# SoC_FPGA_128-131_GTY.net
KiCad netlist of a schematic drawn in Altium Designer
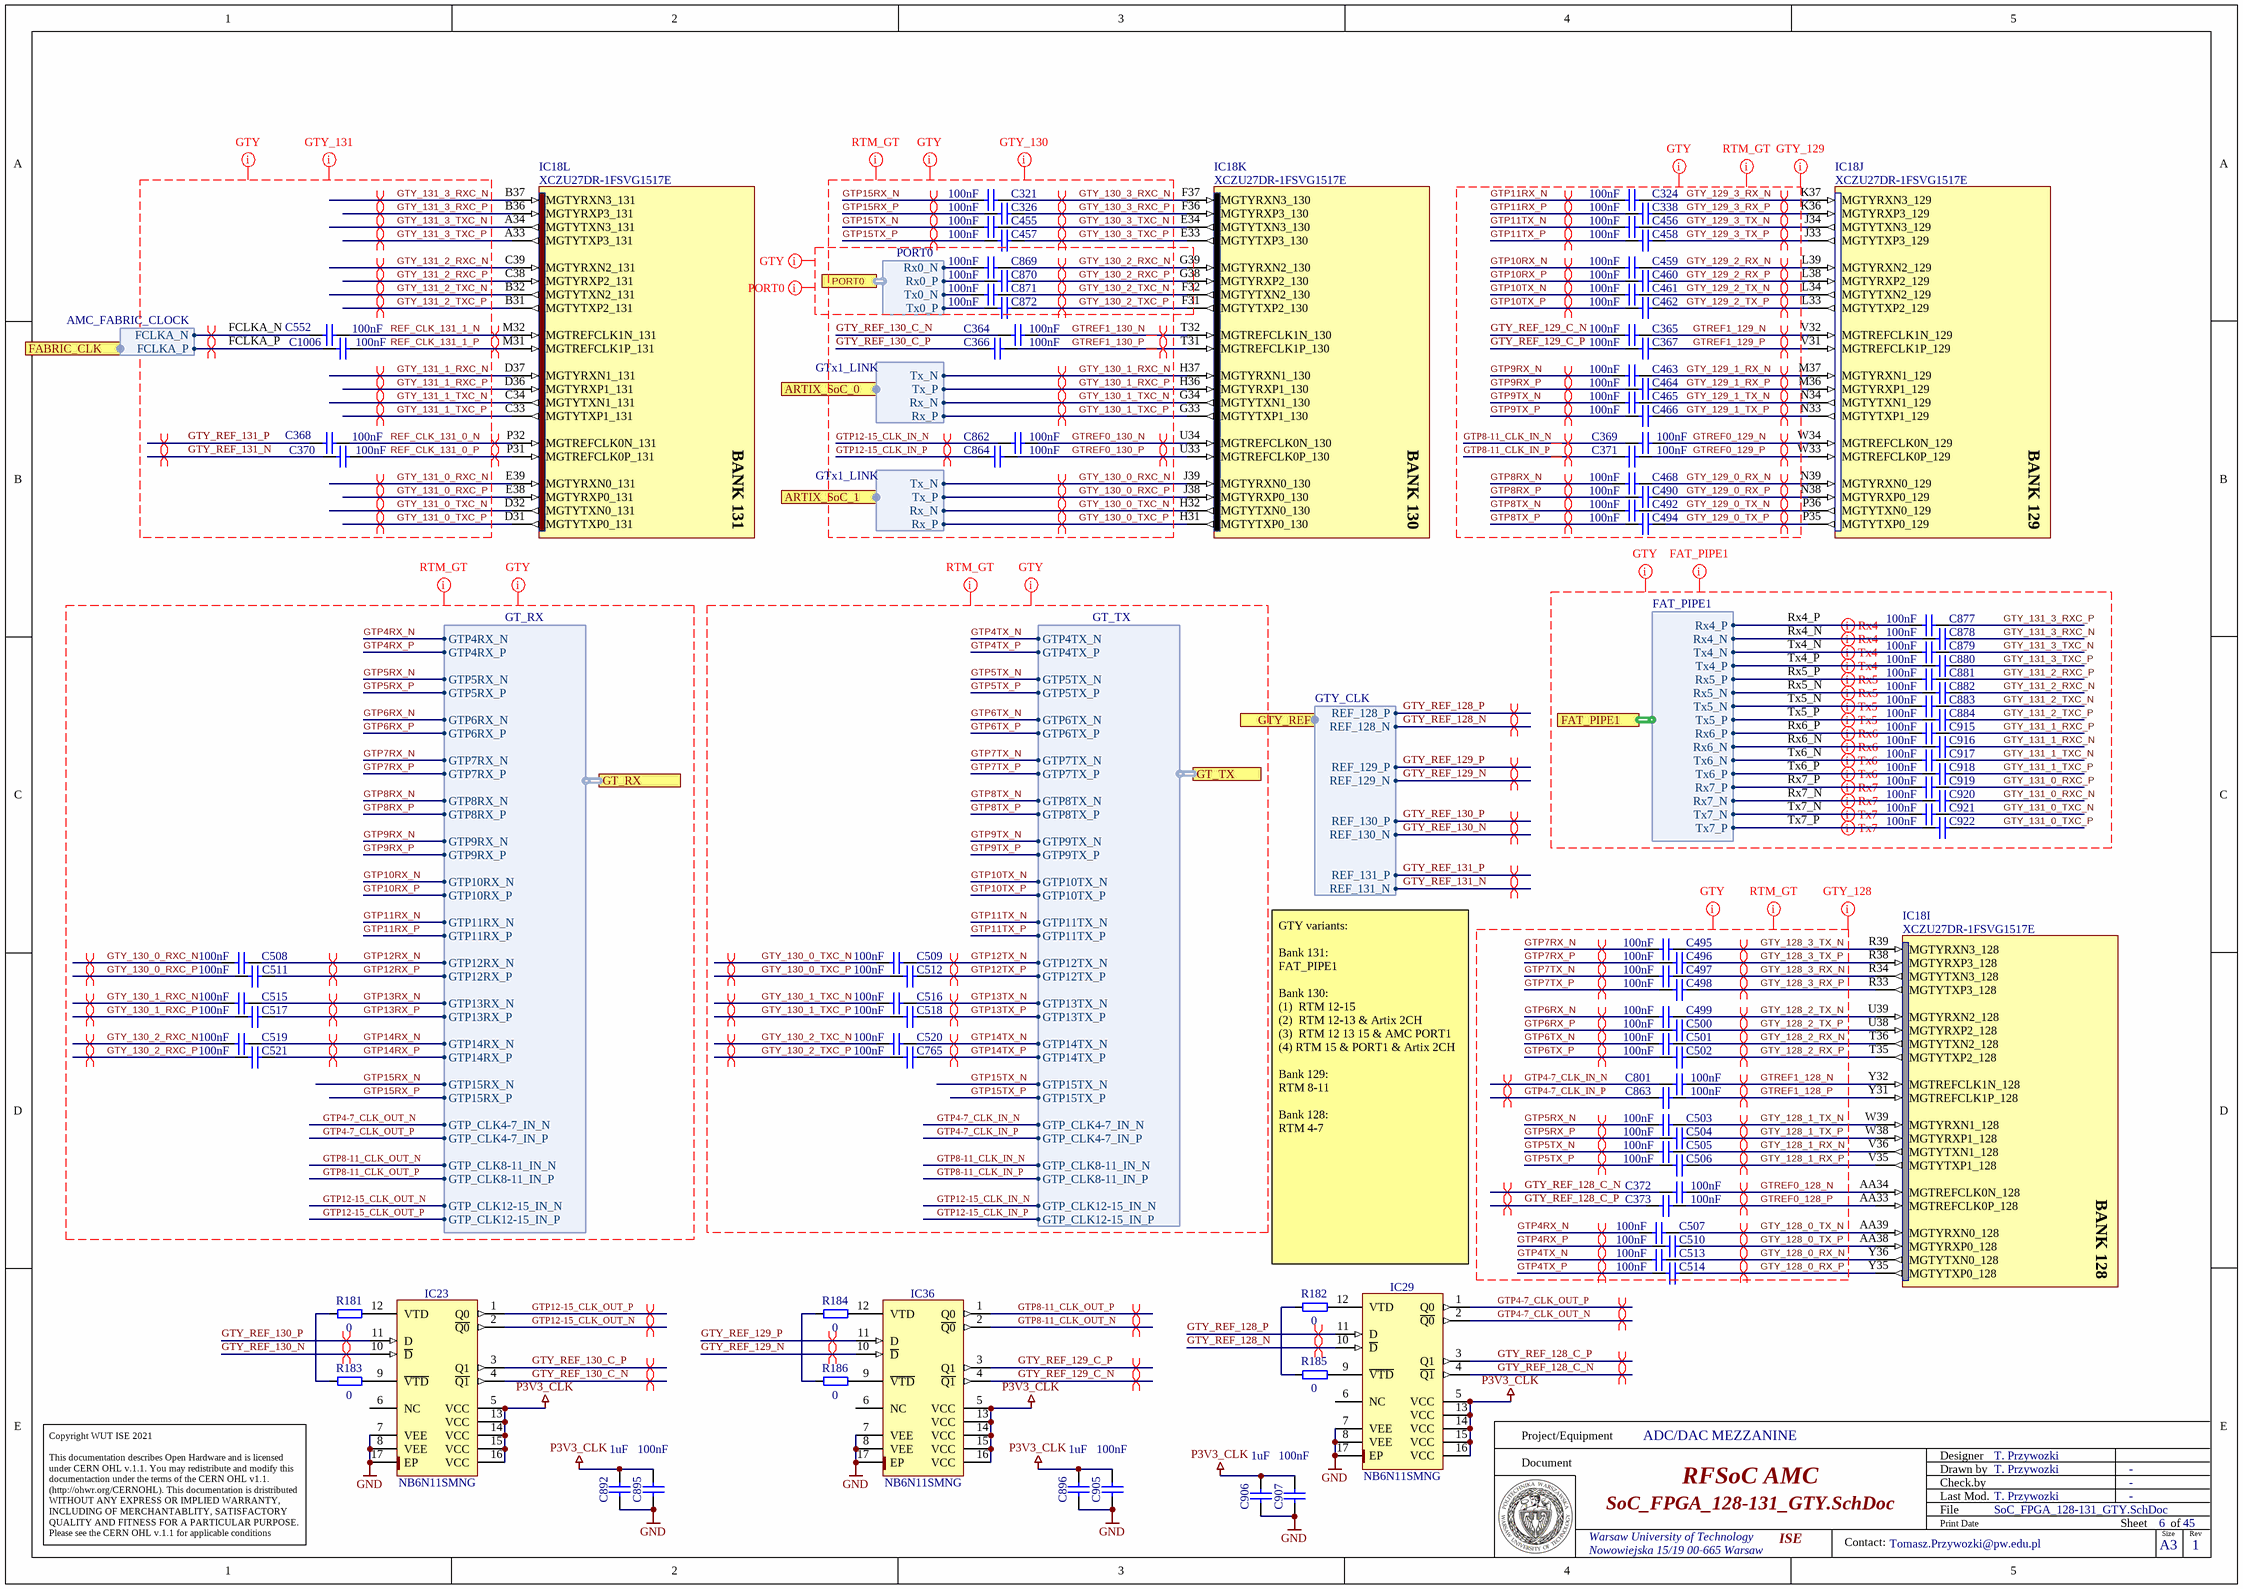
[diagram p0: SoC_FPGA_128-131_GTY.SchDoc]

(export (version "E")
  (design (tool "Eeschema 10.0.6"))
  (components
    (comp (ref "C321")
      (value "100nF")
      (footprint "CAPC0603X33N")
      (description "Non-polarised capacitor")
      (fields
        (field (name "MANUFACTURER PART NUMBER") "CC0201_100NF_6.3V_10%_X5R")
        (field (name "MANUFACTURER") "GENERIC")
        (field (name "AUTHOR") "CERN DEM JLC")
      )
      (libsource (lib "Capacitors") (part "Capacitor - non polarized"))
    )
    (comp (ref "C324")
      (value "100nF")
      (footprint "CAPC0603X33N")
      (description "Non-polarised capacitor")
      (fields
        (field (name "MANUFACTURER PART NUMBER") "CC0201_100NF_6.3V_10%_X5R")
        (field (name "MANUFACTURER") "GENERIC")
        (field (name "AUTHOR") "CERN DEM JLC")
      )
      (libsource (lib "Capacitors") (part "Capacitor - non polarized"))
    )
    (comp (ref "C326")
      (value "100nF")
      (footprint "CAPC0603X33N")
      (description "Non-polarised capacitor")
      (fields
        (field (name "MANUFACTURER PART NUMBER") "CC0201_100NF_6.3V_10%_X5R")
        (field (name "MANUFACTURER") "GENERIC")
        (field (name "AUTHOR") "CERN DEM JLC")
      )
      (libsource (lib "Capacitors") (part "Capacitor - non polarized"))
    )
    (comp (ref "C338")
      (value "100nF")
      (footprint "CAPC0603X33N")
      (description "Non-polarised capacitor")
      (fields
        (field (name "MANUFACTURER PART NUMBER") "CC0201_100NF_6.3V_10%_X5R")
        (field (name "MANUFACTURER") "GENERIC")
        (field (name "AUTHOR") "CERN DEM JLC")
      )
      (libsource (lib "Capacitors") (part "Capacitor - non polarized"))
    )
    (comp (ref "C364")
      (value "100nF")
      (footprint "CAPC0603X33N")
      (description "Non-polarised capacitor")
      (fields
        (field (name "PART NUMBER") "CC0201_100NF_6.3V_10%_X5R")
        (field (name "VOLTAGE") "6.3V")
        (field (name "AUTHOR") "CERN DEM JLC")
      )
      (libsource (lib "Capacitors") (part "Capacitor - non polarized"))
    )
    (comp (ref "C365")
      (value "100nF")
      (footprint "CAPC0603X33N")
      (description "Non-polarised capacitor")
      (fields
        (field (name "MANUFACTURER PART NUMBER") "CC0201_100NF_6.3V_10%_X5R")
        (field (name "MANUFACTURER") "GENERIC")
        (field (name "AUTHOR") "CERN DEM JLC")
      )
      (libsource (lib "Capacitors") (part "Capacitor - non polarized"))
    )
    (comp (ref "C366")
      (value "100nF")
      (footprint "CAPC0603X33N")
      (description "Non-polarised capacitor")
      (fields
        (field (name "PART NUMBER") "CC0201_100NF_6.3V_10%_X5R")
        (field (name "VOLTAGE") "6.3V")
        (field (name "AUTHOR") "CERN DEM JLC")
      )
      (libsource (lib "Capacitors") (part "Capacitor - non polarized"))
    )
    (comp (ref "C367")
      (value "100nF")
      (footprint "CAPC0603X33N")
      (description "Non-polarised capacitor")
      (fields
        (field (name "MANUFACTURER PART NUMBER") "CC0201_100NF_6.3V_10%_X5R")
        (field (name "MANUFACTURER") "GENERIC")
        (field (name "AUTHOR") "CERN DEM JLC")
      )
      (libsource (lib "Capacitors") (part "Capacitor - non polarized"))
    )
    (comp (ref "C368")
      (value "100nF")
      (footprint "CAPC0603X33N")
      (description "Non-polarised capacitor")
      (fields
        (field (name "MANUFACTURER PART NUMBER") "CC0201_100NF_6.3V_10%_X5R")
        (field (name "MANUFACTURER") "GENERIC")
        (field (name "AUTHOR") "CERN DEM JLC")
      )
      (libsource (lib "Capacitors") (part "Capacitor - non polarized"))
    )
    (comp (ref "C369")
      (value "100nF")
      (footprint "CAPC0603X33N")
      (description "Non-polarised capacitor")
      (fields
        (field (name "PART NUMBER") "CC0201_100NF_6.3V_10%_X5R")
        (field (name "VOLTAGE") "6.3V")
        (field (name "AUTHOR") "CERN DEM JLC")
      )
      (libsource (lib "Capacitors") (part "Capacitor - non polarized"))
    )
    (comp (ref "C370")
      (value "100nF")
      (footprint "CAPC0603X33N")
      (description "Non-polarised capacitor")
      (fields
        (field (name "MANUFACTURER PART NUMBER") "CC0201_100NF_6.3V_10%_X5R")
        (field (name "MANUFACTURER") "GENERIC")
        (field (name "AUTHOR") "CERN DEM JLC")
      )
      (libsource (lib "Capacitors") (part "Capacitor - non polarized"))
    )
    (comp (ref "C371")
      (value "100nF")
      (footprint "CAPC0603X33N")
      (description "Non-polarised capacitor")
      (fields
        (field (name "PART NUMBER") "CC0201_100NF_6.3V_10%_X5R")
        (field (name "VOLTAGE") "6.3V")
        (field (name "AUTHOR") "CERN DEM JLC")
      )
      (libsource (lib "Capacitors") (part "Capacitor - non polarized"))
    )
    (comp (ref "C372")
      (value "100nF")
      (footprint "CAPC0603X33N")
      (description "Non-polarised capacitor")
      (fields
        (field (name "PART NUMBER") "CC0201_100NF_6.3V_10%_X5R")
        (field (name "VOLTAGE") "6.3V")
        (field (name "AUTHOR") "CERN DEM JLC")
      )
      (libsource (lib "Capacitors") (part "Capacitor - non polarized"))
    )
    (comp (ref "C373")
      (value "100nF")
      (footprint "CAPC0603X33N")
      (description "Non-polarised capacitor")
      (fields
        (field (name "PART NUMBER") "CC0201_100NF_6.3V_10%_X5R")
        (field (name "VOLTAGE") "6.3V")
        (field (name "AUTHOR") "CERN DEM JLC")
      )
      (libsource (lib "Capacitors") (part "Capacitor - non polarized"))
    )
    (comp (ref "C455")
      (value "100nF")
      (footprint "CAPC0603X33N")
      (description "Non-polarised capacitor")
      (fields
        (field (name "MANUFACTURER PART NUMBER") "CC0201_100NF_6.3V_10%_X5R")
        (field (name "MANUFACTURER") "GENERIC")
        (field (name "AUTHOR") "CERN DEM JLC")
      )
      (libsource (lib "Capacitors") (part "Capacitor - non polarized"))
    )
    (comp (ref "C456")
      (value "100nF")
      (footprint "CAPC0603X33N")
      (description "Non-polarised capacitor")
      (fields
        (field (name "MANUFACTURER PART NUMBER") "CC0201_100NF_6.3V_10%_X5R")
        (field (name "MANUFACTURER") "GENERIC")
        (field (name "AUTHOR") "CERN DEM JLC")
      )
      (libsource (lib "Capacitors") (part "Capacitor - non polarized"))
    )
    (comp (ref "C457")
      (value "100nF")
      (footprint "CAPC0603X33N")
      (description "Non-polarised capacitor")
      (fields
        (field (name "MANUFACTURER PART NUMBER") "CC0201_100NF_6.3V_10%_X5R")
        (field (name "MANUFACTURER") "GENERIC")
        (field (name "AUTHOR") "CERN DEM JLC")
      )
      (libsource (lib "Capacitors") (part "Capacitor - non polarized"))
    )
    (comp (ref "C458")
      (value "100nF")
      (footprint "CAPC0603X33N")
      (description "Non-polarised capacitor")
      (fields
        (field (name "MANUFACTURER PART NUMBER") "CC0201_100NF_6.3V_10%_X5R")
        (field (name "MANUFACTURER") "GENERIC")
        (field (name "AUTHOR") "CERN DEM JLC")
      )
      (libsource (lib "Capacitors") (part "Capacitor - non polarized"))
    )
    (comp (ref "C459")
      (value "100nF")
      (footprint "CAPC0603X33N")
      (description "Non-polarised capacitor")
      (fields
        (field (name "MANUFACTURER PART NUMBER") "CC0201_100NF_6.3V_10%_X5R")
        (field (name "MANUFACTURER") "GENERIC")
        (field (name "AUTHOR") "CERN DEM JLC")
      )
      (libsource (lib "Capacitors") (part "Capacitor - non polarized"))
    )
    (comp (ref "C460")
      (value "100nF")
      (footprint "CAPC0603X33N")
      (description "Non-polarised capacitor")
      (fields
        (field (name "MANUFACTURER PART NUMBER") "CC0201_100NF_6.3V_10%_X5R")
        (field (name "MANUFACTURER") "GENERIC")
        (field (name "AUTHOR") "CERN DEM JLC")
      )
      (libsource (lib "Capacitors") (part "Capacitor - non polarized"))
    )
    (comp (ref "C461")
      (value "100nF")
      (footprint "CAPC0603X33N")
      (description "Non-polarised capacitor")
      (fields
        (field (name "MANUFACTURER PART NUMBER") "CC0201_100NF_6.3V_10%_X5R")
        (field (name "MANUFACTURER") "GENERIC")
        (field (name "AUTHOR") "CERN DEM JLC")
      )
      (libsource (lib "Capacitors") (part "Capacitor - non polarized"))
    )
    (comp (ref "C462")
      (value "100nF")
      (footprint "CAPC0603X33N")
      (description "Non-polarised capacitor")
      (fields
        (field (name "MANUFACTURER PART NUMBER") "CC0201_100NF_6.3V_10%_X5R")
        (field (name "MANUFACTURER") "GENERIC")
        (field (name "AUTHOR") "CERN DEM JLC")
      )
      (libsource (lib "Capacitors") (part "Capacitor - non polarized"))
    )
    (comp (ref "C463")
      (value "100nF")
      (footprint "CAPC0603X33N")
      (description "Non-polarised capacitor")
      (fields
        (field (name "MANUFACTURER PART NUMBER") "CC0201_100NF_6.3V_10%_X5R")
        (field (name "MANUFACTURER") "GENERIC")
        (field (name "AUTHOR") "CERN DEM JLC")
      )
      (libsource (lib "Capacitors") (part "Capacitor - non polarized"))
    )
    (comp (ref "C464")
      (value "100nF")
      (footprint "CAPC0603X33N")
      (description "Non-polarised capacitor")
      (fields
        (field (name "MANUFACTURER PART NUMBER") "CC0201_100NF_6.3V_10%_X5R")
        (field (name "MANUFACTURER") "GENERIC")
        (field (name "AUTHOR") "CERN DEM JLC")
      )
      (libsource (lib "Capacitors") (part "Capacitor - non polarized"))
    )
    (comp (ref "C465")
      (value "100nF")
      (footprint "CAPC0603X33N")
      (description "Non-polarised capacitor")
      (fields
        (field (name "MANUFACTURER PART NUMBER") "CC0201_100NF_6.3V_10%_X5R")
        (field (name "MANUFACTURER") "GENERIC")
        (field (name "AUTHOR") "CERN DEM JLC")
      )
      (libsource (lib "Capacitors") (part "Capacitor - non polarized"))
    )
    (comp (ref "C466")
      (value "100nF")
      (footprint "CAPC0603X33N")
      (description "Non-polarised capacitor")
      (fields
        (field (name "MANUFACTURER PART NUMBER") "CC0201_100NF_6.3V_10%_X5R")
        (field (name "MANUFACTURER") "GENERIC")
        (field (name "AUTHOR") "CERN DEM JLC")
      )
      (libsource (lib "Capacitors") (part "Capacitor - non polarized"))
    )
    (comp (ref "C468")
      (value "100nF")
      (footprint "CAPC0603X33N")
      (description "Non-polarised capacitor")
      (fields
        (field (name "MANUFACTURER PART NUMBER") "CC0201_100NF_6.3V_10%_X5R")
        (field (name "MANUFACTURER") "GENERIC")
        (field (name "AUTHOR") "CERN DEM JLC")
      )
      (libsource (lib "Capacitors") (part "Capacitor - non polarized"))
    )
    (comp (ref "C490")
      (value "100nF")
      (footprint "CAPC0603X33N")
      (description "Non-polarised capacitor")
      (fields
        (field (name "MANUFACTURER PART NUMBER") "CC0201_100NF_6.3V_10%_X5R")
        (field (name "MANUFACTURER") "GENERIC")
        (field (name "AUTHOR") "CERN DEM JLC")
      )
      (libsource (lib "Capacitors") (part "Capacitor - non polarized"))
    )
    (comp (ref "C492")
      (value "100nF")
      (footprint "CAPC0603X33N")
      (description "Non-polarised capacitor")
      (fields
        (field (name "MANUFACTURER PART NUMBER") "CC0201_100NF_6.3V_10%_X5R")
        (field (name "MANUFACTURER") "GENERIC")
        (field (name "AUTHOR") "CERN DEM JLC")
      )
      (libsource (lib "Capacitors") (part "Capacitor - non polarized"))
    )
    (comp (ref "C494")
      (value "100nF")
      (footprint "CAPC0603X33N")
      (description "Non-polarised capacitor")
      (fields
        (field (name "MANUFACTURER PART NUMBER") "CC0201_100NF_6.3V_10%_X5R")
        (field (name "MANUFACTURER") "GENERIC")
        (field (name "AUTHOR") "CERN DEM JLC")
      )
      (libsource (lib "Capacitors") (part "Capacitor - non polarized"))
    )
    (comp (ref "C495")
      (value "100nF")
      (footprint "CAPC0603X33N")
      (description "Non-polarised capacitor")
      (fields
        (field (name "MANUFACTURER PART NUMBER") "CC0201_100NF_6.3V_10%_X5R")
        (field (name "MANUFACTURER") "GENERIC")
        (field (name "AUTHOR") "CERN DEM JLC")
      )
      (libsource (lib "Capacitors") (part "Capacitor - non polarized"))
    )
    (comp (ref "C496")
      (value "100nF")
      (footprint "CAPC0603X33N")
      (description "Non-polarised capacitor")
      (fields
        (field (name "MANUFACTURER PART NUMBER") "CC0201_100NF_6.3V_10%_X5R")
        (field (name "MANUFACTURER") "GENERIC")
        (field (name "AUTHOR") "CERN DEM JLC")
      )
      (libsource (lib "Capacitors") (part "Capacitor - non polarized"))
    )
    (comp (ref "C497")
      (value "100nF")
      (footprint "CAPC0603X33N")
      (description "Non-polarised capacitor")
      (fields
        (field (name "MANUFACTURER PART NUMBER") "CC0201_100NF_6.3V_10%_X5R")
        (field (name "MANUFACTURER") "GENERIC")
        (field (name "AUTHOR") "CERN DEM JLC")
      )
      (libsource (lib "Capacitors") (part "Capacitor - non polarized"))
    )
    (comp (ref "C498")
      (value "100nF")
      (footprint "CAPC0603X33N")
      (description "Non-polarised capacitor")
      (fields
        (field (name "MANUFACTURER PART NUMBER") "CC0201_100NF_6.3V_10%_X5R")
        (field (name "MANUFACTURER") "GENERIC")
        (field (name "AUTHOR") "CERN DEM JLC")
      )
      (libsource (lib "Capacitors") (part "Capacitor - non polarized"))
    )
    (comp (ref "C499")
      (value "100nF")
      (footprint "CAPC0603X33N")
      (description "Non-polarised capacitor")
      (fields
        (field (name "MANUFACTURER PART NUMBER") "CC0201_100NF_6.3V_10%_X5R")
        (field (name "MANUFACTURER") "GENERIC")
        (field (name "AUTHOR") "CERN DEM JLC")
      )
      (libsource (lib "Capacitors") (part "Capacitor - non polarized"))
    )
    (comp (ref "C500")
      (value "100nF")
      (footprint "CAPC0603X33N")
      (description "Non-polarised capacitor")
      (fields
        (field (name "MANUFACTURER PART NUMBER") "CC0201_100NF_6.3V_10%_X5R")
        (field (name "MANUFACTURER") "GENERIC")
        (field (name "AUTHOR") "CERN DEM JLC")
      )
      (libsource (lib "Capacitors") (part "Capacitor - non polarized"))
    )
    (comp (ref "C501")
      (value "100nF")
      (footprint "CAPC0603X33N")
      (description "Non-polarised capacitor")
      (fields
        (field (name "MANUFACTURER PART NUMBER") "CC0201_100NF_6.3V_10%_X5R")
        (field (name "MANUFACTURER") "GENERIC")
        (field (name "AUTHOR") "CERN DEM JLC")
      )
      (libsource (lib "Capacitors") (part "Capacitor - non polarized"))
    )
    (comp (ref "C502")
      (value "100nF")
      (footprint "CAPC0603X33N")
      (description "Non-polarised capacitor")
      (fields
        (field (name "MANUFACTURER PART NUMBER") "CC0201_100NF_6.3V_10%_X5R")
        (field (name "MANUFACTURER") "GENERIC")
        (field (name "AUTHOR") "CERN DEM JLC")
      )
      (libsource (lib "Capacitors") (part "Capacitor - non polarized"))
    )
    (comp (ref "C503")
      (value "100nF")
      (footprint "CAPC0603X33N")
      (description "Non-polarised capacitor")
      (fields
        (field (name "MANUFACTURER PART NUMBER") "CC0201_100NF_6.3V_10%_X5R")
        (field (name "MANUFACTURER") "GENERIC")
        (field (name "AUTHOR") "CERN DEM JLC")
      )
      (libsource (lib "Capacitors") (part "Capacitor - non polarized"))
    )
    (comp (ref "C504")
      (value "100nF")
      (footprint "CAPC0603X33N")
      (description "Non-polarised capacitor")
      (fields
        (field (name "MANUFACTURER PART NUMBER") "CC0201_100NF_6.3V_10%_X5R")
        (field (name "MANUFACTURER") "GENERIC")
        (field (name "AUTHOR") "CERN DEM JLC")
      )
      (libsource (lib "Capacitors") (part "Capacitor - non polarized"))
    )
    (comp (ref "C505")
      (value "100nF")
      (footprint "CAPC0603X33N")
      (description "Non-polarised capacitor")
      (fields
        (field (name "MANUFACTURER PART NUMBER") "CC0201_100NF_6.3V_10%_X5R")
        (field (name "MANUFACTURER") "GENERIC")
        (field (name "AUTHOR") "CERN DEM JLC")
      )
      (libsource (lib "Capacitors") (part "Capacitor - non polarized"))
    )
    (comp (ref "C506")
      (value "100nF")
      (footprint "CAPC0603X33N")
      (description "Non-polarised capacitor")
      (fields
        (field (name "MANUFACTURER PART NUMBER") "CC0201_100NF_6.3V_10%_X5R")
        (field (name "MANUFACTURER") "GENERIC")
        (field (name "AUTHOR") "CERN DEM JLC")
      )
      (libsource (lib "Capacitors") (part "Capacitor - non polarized"))
    )
    (comp (ref "C507")
      (value "100nF")
      (footprint "CAPC0603X33N")
      (description "Non-polarised capacitor")
      (fields
        (field (name "MANUFACTURER PART NUMBER") "CC0201_100NF_6.3V_10%_X5R")
        (field (name "MANUFACTURER") "GENERIC")
        (field (name "AUTHOR") "CERN DEM JLC")
      )
      (libsource (lib "Capacitors") (part "Capacitor - non polarized"))
    )
    (comp (ref "C508")
      (value "100nF")
      (footprint "CAPC0603X33N")
      (description "Non-polarised capacitor")
      (fields
        (field (name "MANUFACTURER PART NUMBER") "CC0201_100NF_6.3V_10%_X5R")
        (field (name "MANUFACTURER") "GENERIC")
        (field (name "AUTHOR") "CERN DEM JLC")
      )
      (libsource (lib "Capacitors") (part "Capacitor - non polarized"))
    )
    (comp (ref "C509")
      (value "100nF")
      (footprint "CAPC0603X33N")
      (description "Non-polarised capacitor")
      (fields
        (field (name "MANUFACTURER PART NUMBER") "CC0201_100NF_6.3V_10%_X5R")
        (field (name "MANUFACTURER") "GENERIC")
        (field (name "AUTHOR") "CERN DEM JLC")
      )
      (libsource (lib "Capacitors") (part "Capacitor - non polarized"))
    )
    (comp (ref "C510")
      (value "100nF")
      (footprint "CAPC0603X33N")
      (description "Non-polarised capacitor")
      (fields
        (field (name "MANUFACTURER PART NUMBER") "CC0201_100NF_6.3V_10%_X5R")
        (field (name "MANUFACTURER") "GENERIC")
        (field (name "AUTHOR") "CERN DEM JLC")
      )
      (libsource (lib "Capacitors") (part "Capacitor - non polarized"))
    )
    (comp (ref "C511")
      (value "100nF")
      (footprint "CAPC0603X33N")
      (description "Non-polarised capacitor")
      (fields
        (field (name "MANUFACTURER PART NUMBER") "CC0201_100NF_6.3V_10%_X5R")
        (field (name "MANUFACTURER") "GENERIC")
        (field (name "AUTHOR") "CERN DEM JLC")
      )
      (libsource (lib "Capacitors") (part "Capacitor - non polarized"))
    )
    (comp (ref "C512")
      (value "100nF")
      (footprint "CAPC0603X33N")
      (description "Non-polarised capacitor")
      (fields
        (field (name "MANUFACTURER PART NUMBER") "CC0201_100NF_6.3V_10%_X5R")
        (field (name "MANUFACTURER") "GENERIC")
        (field (name "AUTHOR") "CERN DEM JLC")
      )
      (libsource (lib "Capacitors") (part "Capacitor - non polarized"))
    )
    (comp (ref "C513")
      (value "100nF")
      (footprint "CAPC0603X33N")
      (description "Non-polarised capacitor")
      (fields
        (field (name "MANUFACTURER PART NUMBER") "CC0201_100NF_6.3V_10%_X5R")
        (field (name "MANUFACTURER") "GENERIC")
        (field (name "AUTHOR") "CERN DEM JLC")
      )
      (libsource (lib "Capacitors") (part "Capacitor - non polarized"))
    )
    (comp (ref "C514")
      (value "100nF")
      (footprint "CAPC0603X33N")
      (description "Non-polarised capacitor")
      (fields
        (field (name "MANUFACTURER PART NUMBER") "CC0201_100NF_6.3V_10%_X5R")
        (field (name "MANUFACTURER") "GENERIC")
        (field (name "AUTHOR") "CERN DEM JLC")
      )
      (libsource (lib "Capacitors") (part "Capacitor - non polarized"))
    )
    (comp (ref "C515")
      (value "100nF")
      (footprint "CAPC0603X33N")
      (description "Non-polarised capacitor")
      (fields
        (field (name "MANUFACTURER PART NUMBER") "CC0201_100NF_6.3V_10%_X5R")
        (field (name "MANUFACTURER") "GENERIC")
        (field (name "AUTHOR") "CERN DEM JLC")
      )
      (libsource (lib "Capacitors") (part "Capacitor - non polarized"))
    )
    (comp (ref "C516")
      (value "100nF")
      (footprint "CAPC0603X33N")
      (description "Non-polarised capacitor")
      (fields
        (field (name "MANUFACTURER PART NUMBER") "CC0201_100NF_6.3V_10%_X5R")
        (field (name "MANUFACTURER") "GENERIC")
        (field (name "AUTHOR") "CERN DEM JLC")
      )
      (libsource (lib "Capacitors") (part "Capacitor - non polarized"))
    )
    (comp (ref "C517")
      (value "100nF")
      (footprint "CAPC0603X33N")
      (description "Non-polarised capacitor")
      (fields
        (field (name "MANUFACTURER PART NUMBER") "CC0201_100NF_6.3V_10%_X5R")
        (field (name "MANUFACTURER") "GENERIC")
        (field (name "AUTHOR") "CERN DEM JLC")
      )
      (libsource (lib "Capacitors") (part "Capacitor - non polarized"))
    )
    (comp (ref "C518")
      (value "100nF")
      (footprint "CAPC0603X33N")
      (description "Non-polarised capacitor")
      (fields
        (field (name "MANUFACTURER PART NUMBER") "CC0201_100NF_6.3V_10%_X5R")
        (field (name "MANUFACTURER") "GENERIC")
        (field (name "AUTHOR") "CERN DEM JLC")
      )
      (libsource (lib "Capacitors") (part "Capacitor - non polarized"))
    )
    (comp (ref "C519")
      (value "100nF")
      (footprint "CAPC0603X33N")
      (description "Non-polarised capacitor")
      (fields
        (field (name "MANUFACTURER PART NUMBER") "CC0201_100NF_6.3V_10%_X5R")
        (field (name "MANUFACTURER") "GENERIC")
        (field (name "AUTHOR") "CERN DEM JLC")
      )
      (libsource (lib "Capacitors") (part "Capacitor - non polarized"))
    )
    (comp (ref "C520")
      (value "100nF")
      (footprint "CAPC0603X33N")
      (description "Non-polarised capacitor")
      (fields
        (field (name "MANUFACTURER PART NUMBER") "CC0201_100NF_6.3V_10%_X5R")
        (field (name "MANUFACTURER") "GENERIC")
        (field (name "AUTHOR") "CERN DEM JLC")
      )
      (libsource (lib "Capacitors") (part "Capacitor - non polarized"))
    )
    (comp (ref "C521")
      (value "100nF")
      (footprint "CAPC0603X33N")
      (description "Non-polarised capacitor")
      (fields
        (field (name "MANUFACTURER PART NUMBER") "CC0201_100NF_6.3V_10%_X5R")
        (field (name "MANUFACTURER") "GENERIC")
        (field (name "AUTHOR") "CERN DEM JLC")
      )
      (libsource (lib "Capacitors") (part "Capacitor - non polarized"))
    )
    (comp (ref "C552")
      (value "100nF")
      (footprint "CAPC0603X33N")
      (description "Non-polarised capacitor")
      (fields
        (field (name "MANUFACTURER PART NUMBER") "CC0201_100NF_6.3V_10%_X5R")
        (field (name "MANUFACTURER") "GENERIC")
        (field (name "AUTHOR") "CERN DEM JLC")
      )
      (libsource (lib "Capacitors") (part "Capacitor - non polarized"))
    )
    (comp (ref "C765")
      (value "100nF")
      (footprint "CAPC0603X33N")
      (description "Non-polarised capacitor")
      (fields
        (field (name "MANUFACTURER PART NUMBER") "CC0201_100NF_6.3V_10%_X5R")
        (field (name "MANUFACTURER") "GENERIC")
        (field (name "AUTHOR") "CERN DEM JLC")
      )
      (libsource (lib "Capacitors") (part "Capacitor - non polarized"))
    )
    (comp (ref "C801")
      (value "100nF")
      (footprint "CAPC0603X33N")
      (description "Non-polarised capacitor")
      (fields
        (field (name "PART NUMBER") "CC0201_100NF_6.3V_10%_X5R")
        (field (name "VOLTAGE") "6.3V")
        (field (name "AUTHOR") "CERN DEM JLC")
      )
      (libsource (lib "Capacitors") (part "Capacitor - non polarized"))
    )
    (comp (ref "C862")
      (value "100nF")
      (footprint "CAPC0603X33N")
      (description "Non-polarised capacitor")
      (fields
        (field (name "PART NUMBER") "CC0201_100NF_6.3V_10%_X5R")
        (field (name "VOLTAGE") "6.3V")
        (field (name "AUTHOR") "CERN DEM JLC")
      )
      (libsource (lib "Capacitors") (part "Capacitor - non polarized"))
    )
    (comp (ref "C863")
      (value "100nF")
      (footprint "CAPC0603X33N")
      (description "Non-polarised capacitor")
      (fields
        (field (name "PART NUMBER") "CC0201_100NF_6.3V_10%_X5R")
        (field (name "VOLTAGE") "6.3V")
        (field (name "AUTHOR") "CERN DEM JLC")
      )
      (libsource (lib "Capacitors") (part "Capacitor - non polarized"))
    )
    (comp (ref "C864")
      (value "100nF")
      (footprint "CAPC0603X33N")
      (description "Non-polarised capacitor")
      (fields
        (field (name "PART NUMBER") "CC0201_100NF_6.3V_10%_X5R")
        (field (name "VOLTAGE") "6.3V")
        (field (name "AUTHOR") "CERN DEM JLC")
      )
      (libsource (lib "Capacitors") (part "Capacitor - non polarized"))
    )
    (comp (ref "C869")
      (value "100nF")
      (footprint "CAPC0603X33N")
      (description "Non-polarised capacitor")
      (fields
        (field (name "MANUFACTURER PART NUMBER") "CC0201_100NF_6.3V_10%_X5R")
        (field (name "MANUFACTURER") "GENERIC")
        (field (name "AUTHOR") "CERN DEM JLC")
      )
      (libsource (lib "Capacitors") (part "Capacitor - non polarized"))
    )
    (comp (ref "C870")
      (value "100nF")
      (footprint "CAPC0603X33N")
      (description "Non-polarised capacitor")
      (fields
        (field (name "MANUFACTURER PART NUMBER") "CC0201_100NF_6.3V_10%_X5R")
        (field (name "MANUFACTURER") "GENERIC")
        (field (name "AUTHOR") "CERN DEM JLC")
      )
      (libsource (lib "Capacitors") (part "Capacitor - non polarized"))
    )
    (comp (ref "C871")
      (value "100nF")
      (footprint "CAPC0603X33N")
      (description "Non-polarised capacitor")
      (fields
        (field (name "MANUFACTURER PART NUMBER") "CC0201_100NF_6.3V_10%_X5R")
        (field (name "MANUFACTURER") "GENERIC")
        (field (name "AUTHOR") "CERN DEM JLC")
      )
      (libsource (lib "Capacitors") (part "Capacitor - non polarized"))
    )
    (comp (ref "C872")
      (value "100nF")
      (footprint "CAPC0603X33N")
      (description "Non-polarised capacitor")
      (fields
        (field (name "MANUFACTURER PART NUMBER") "CC0201_100NF_6.3V_10%_X5R")
        (field (name "MANUFACTURER") "GENERIC")
        (field (name "AUTHOR") "CERN DEM JLC")
      )
      (libsource (lib "Capacitors") (part "Capacitor - non polarized"))
    )
    (comp (ref "C877")
      (value "100nF")
      (footprint "CAPC0603X33N")
      (description "Non-polarised capacitor")
      (fields
        (field (name "MANUFACTURER PART NUMBER") "CC0201_100NF_6.3V_10%_X5R")
        (field (name "MANUFACTURER") "GENERIC")
        (field (name "AUTHOR") "CERN DEM JLC")
      )
      (libsource (lib "Capacitors") (part "Capacitor - non polarized"))
    )
    (comp (ref "C878")
      (value "100nF")
      (footprint "CAPC0603X33N")
      (description "Non-polarised capacitor")
      (fields
        (field (name "MANUFACTURER PART NUMBER") "CC0201_100NF_6.3V_10%_X5R")
        (field (name "MANUFACTURER") "GENERIC")
        (field (name "AUTHOR") "CERN DEM JLC")
      )
      (libsource (lib "Capacitors") (part "Capacitor - non polarized"))
    )
    (comp (ref "C879")
      (value "100nF")
      (footprint "CAPC0603X33N")
      (description "Non-polarised capacitor")
      (fields
        (field (name "MANUFACTURER PART NUMBER") "CC0201_100NF_6.3V_10%_X5R")
        (field (name "MANUFACTURER") "GENERIC")
        (field (name "AUTHOR") "CERN DEM JLC")
      )
      (libsource (lib "Capacitors") (part "Capacitor - non polarized"))
    )
    (comp (ref "C880")
      (value "100nF")
      (footprint "CAPC0603X33N")
      (description "Non-polarised capacitor")
      (fields
        (field (name "MANUFACTURER PART NUMBER") "CC0201_100NF_6.3V_10%_X5R")
        (field (name "MANUFACTURER") "GENERIC")
        (field (name "AUTHOR") "CERN DEM JLC")
      )
      (libsource (lib "Capacitors") (part "Capacitor - non polarized"))
    )
    (comp (ref "C881")
      (value "100nF")
      (footprint "CAPC0603X33N")
      (description "Non-polarised capacitor")
      (fields
        (field (name "MANUFACTURER PART NUMBER") "CC0201_100NF_6.3V_10%_X5R")
        (field (name "MANUFACTURER") "GENERIC")
        (field (name "AUTHOR") "CERN DEM JLC")
      )
      (libsource (lib "Capacitors") (part "Capacitor - non polarized"))
    )
    (comp (ref "C882")
      (value "100nF")
      (footprint "CAPC0603X33N")
      (description "Non-polarised capacitor")
      (fields
        (field (name "MANUFACTURER PART NUMBER") "CC0201_100NF_6.3V_10%_X5R")
        (field (name "MANUFACTURER") "GENERIC")
        (field (name "AUTHOR") "CERN DEM JLC")
      )
      (libsource (lib "Capacitors") (part "Capacitor - non polarized"))
    )
    (comp (ref "C883")
      (value "100nF")
      (footprint "CAPC0603X33N")
      (description "Non-polarised capacitor")
      (fields
        (field (name "MANUFACTURER PART NUMBER") "CC0201_100NF_6.3V_10%_X5R")
        (field (name "MANUFACTURER") "GENERIC")
        (field (name "AUTHOR") "CERN DEM JLC")
      )
      (libsource (lib "Capacitors") (part "Capacitor - non polarized"))
    )
    (comp (ref "C884")
      (value "100nF")
      (footprint "CAPC0603X33N")
      (description "Non-polarised capacitor")
      (fields
        (field (name "MANUFACTURER PART NUMBER") "CC0201_100NF_6.3V_10%_X5R")
        (field (name "MANUFACTURER") "GENERIC")
        (field (name "AUTHOR") "CERN DEM JLC")
      )
      (libsource (lib "Capacitors") (part "Capacitor - non polarized"))
    )
    (comp (ref "C892")
      (value "1uF")
      (footprint "CAPC1005X55N")
      (description "Non-polarised capacitor")
      (fields
        (field (name "MANUFACTURER PART NUMBER") "CC0402_1UF_16V_10%_X5R")
        (field (name "MANUFACTURER") "GENERIC")
        (field (name "AUTHOR") "CERN DEM JLC")
      )
      (libsource (lib "Capacitors") (part "Capacitor - non polarized"))
    )
    (comp (ref "C895")
      (value "100nF")
      (footprint "CAPC0603X33N")
      (description "Non-polarised capacitor")
      (fields
        (field (name "MANUFACTURER PART NUMBER") "CC0201_100NF_6.3V_10%_X5R")
        (field (name "MANUFACTURER") "GENERIC")
        (field (name "AUTHOR") "CERN DEM JLC")
      )
      (libsource (lib "Capacitors") (part "Capacitor - non polarized"))
    )
    (comp (ref "C896")
      (value "1uF")
      (footprint "CAPC1005X55N")
      (description "Non-polarised capacitor")
      (fields
        (field (name "MANUFACTURER PART NUMBER") "CC0402_1UF_16V_10%_X5R")
        (field (name "MANUFACTURER") "GENERIC")
        (field (name "AUTHOR") "CERN DEM JLC")
      )
      (libsource (lib "Capacitors") (part "Capacitor - non polarized"))
    )
    (comp (ref "C905")
      (value "100nF")
      (footprint "CAPC0603X33N")
      (description "Non-polarised capacitor")
      (fields
        (field (name "MANUFACTURER PART NUMBER") "CC0201_100NF_6.3V_10%_X5R")
        (field (name "MANUFACTURER") "GENERIC")
        (field (name "AUTHOR") "CERN DEM JLC")
      )
      (libsource (lib "Capacitors") (part "Capacitor - non polarized"))
    )
    (comp (ref "C906")
      (value "1uF")
      (footprint "CAPC1005X55N")
      (description "Non-polarised capacitor")
      (fields
        (field (name "MANUFACTURER PART NUMBER") "CC0402_1UF_16V_10%_X5R")
        (field (name "MANUFACTURER") "GENERIC")
        (field (name "AUTHOR") "CERN DEM JLC")
      )
      (libsource (lib "Capacitors") (part "Capacitor - non polarized"))
    )
    (comp (ref "C907")
      (value "100nF")
      (footprint "CAPC0603X33N")
      (description "Non-polarised capacitor")
      (fields
        (field (name "MANUFACTURER PART NUMBER") "CC0201_100NF_6.3V_10%_X5R")
        (field (name "MANUFACTURER") "GENERIC")
        (field (name "AUTHOR") "CERN DEM JLC")
      )
      (libsource (lib "Capacitors") (part "Capacitor - non polarized"))
    )
    (comp (ref "C915")
      (value "100nF")
      (footprint "CAPC0603X33N")
      (description "Non-polarised capacitor")
      (fields
        (field (name "MANUFACTURER PART NUMBER") "CC0201_100NF_6.3V_10%_X5R")
        (field (name "MANUFACTURER") "GENERIC")
        (field (name "AUTHOR") "CERN DEM JLC")
      )
      (libsource (lib "Capacitors") (part "Capacitor - non polarized"))
    )
    (comp (ref "C916")
      (value "100nF")
      (footprint "CAPC0603X33N")
      (description "Non-polarised capacitor")
      (fields
        (field (name "MANUFACTURER PART NUMBER") "CC0201_100NF_6.3V_10%_X5R")
        (field (name "MANUFACTURER") "GENERIC")
        (field (name "AUTHOR") "CERN DEM JLC")
      )
      (libsource (lib "Capacitors") (part "Capacitor - non polarized"))
    )
    (comp (ref "C917")
      (value "100nF")
      (footprint "CAPC0603X33N")
      (description "Non-polarised capacitor")
      (fields
        (field (name "MANUFACTURER PART NUMBER") "CC0201_100NF_6.3V_10%_X5R")
        (field (name "MANUFACTURER") "GENERIC")
        (field (name "AUTHOR") "CERN DEM JLC")
      )
      (libsource (lib "Capacitors") (part "Capacitor - non polarized"))
    )
    (comp (ref "C918")
      (value "100nF")
      (footprint "CAPC0603X33N")
      (description "Non-polarised capacitor")
      (fields
        (field (name "MANUFACTURER PART NUMBER") "CC0201_100NF_6.3V_10%_X5R")
        (field (name "MANUFACTURER") "GENERIC")
        (field (name "AUTHOR") "CERN DEM JLC")
      )
      (libsource (lib "Capacitors") (part "Capacitor - non polarized"))
    )
    (comp (ref "C919")
      (value "100nF")
      (footprint "CAPC0603X33N")
      (description "Non-polarised capacitor")
      (fields
        (field (name "MANUFACTURER PART NUMBER") "CC0201_100NF_6.3V_10%_X5R")
        (field (name "MANUFACTURER") "GENERIC")
        (field (name "AUTHOR") "CERN DEM JLC")
      )
      (libsource (lib "Capacitors") (part "Capacitor - non polarized"))
    )
    (comp (ref "C920")
      (value "100nF")
      (footprint "CAPC0603X33N")
      (description "Non-polarised capacitor")
      (fields
        (field (name "MANUFACTURER PART NUMBER") "CC0201_100NF_6.3V_10%_X5R")
        (field (name "MANUFACTURER") "GENERIC")
        (field (name "AUTHOR") "CERN DEM JLC")
      )
      (libsource (lib "Capacitors") (part "Capacitor - non polarized"))
    )
    (comp (ref "C921")
      (value "100nF")
      (footprint "CAPC0603X33N")
      (description "Non-polarised capacitor")
      (fields
        (field (name "MANUFACTURER PART NUMBER") "CC0201_100NF_6.3V_10%_X5R")
        (field (name "MANUFACTURER") "GENERIC")
        (field (name "AUTHOR") "CERN DEM JLC")
      )
      (libsource (lib "Capacitors") (part "Capacitor - non polarized"))
    )
    (comp (ref "C922")
      (value "100nF")
      (footprint "CAPC0603X33N")
      (description "Non-polarised capacitor")
      (fields
        (field (name "MANUFACTURER PART NUMBER") "CC0201_100NF_6.3V_10%_X5R")
        (field (name "MANUFACTURER") "GENERIC")
        (field (name "AUTHOR") "CERN DEM JLC")
      )
      (libsource (lib "Capacitors") (part "Capacitor - non polarized"))
    )
    (comp (ref "C1006")
      (value "100nF")
      (footprint "CAPC0603X33N")
      (description "Non-polarised capacitor")
      (fields
        (field (name "MANUFACTURER PART NUMBER") "CC0201_100NF_6.3V_10%_X5R")
        (field (name "MANUFACTURER") "GENERIC")
        (field (name "AUTHOR") "CERN DEM JLC")
      )
      (libsource (lib "Capacitors") (part "Capacitor - non polarized"))
    )
    (comp (ref "IC18")
      (value "XCZU27DR-1FSVG1517E")
      (footprint "XILINX_FSVG1517 (XCZU27DR)")
      (fields (field (name "MANUFACTURER") "XILINX") (field (name "AUTHOR") "CERN DEM MR"))
      (libsource (lib "ICs And Semiconductors") (part "XCZU27DR-1FSVG1517E"))
    )
    (comp (ref "IC23")
      (value "NB6N11SMNG")
      (footprint "QFN50P300X300X100-17N-S185")
      (description "3.3V 1:2 AnyLevel Input to LVDS Fanout Buffer / Translator")
      (fields (field (name "MANUFACTURER") "ON SEMICONDUCTOR") (field (name "AUTHOR") "CERN DEM JLC"))
      (libsource (lib "ICs And Semiconductors") (part "NB6N11SMN"))
    )
    (comp (ref "IC29")
      (value "NB6N11SMNG")
      (footprint "QFN50P300X300X100-17N-S185")
      (description "3.3V 1:2 AnyLevel Input to LVDS Fanout Buffer / Translator")
      (fields (field (name "MANUFACTURER") "ON SEMICONDUCTOR") (field (name "AUTHOR") "CERN DEM JLC"))
      (libsource (lib "ICs And Semiconductors") (part "NB6N11SMN"))
    )
    (comp (ref "IC36")
      (value "NB6N11SMNG")
      (footprint "QFN50P300X300X100-17N-S185")
      (description "3.3V 1:2 AnyLevel Input to LVDS Fanout Buffer / Translator")
      (fields (field (name "MANUFACTURER") "ON SEMICONDUCTOR") (field (name "AUTHOR") "CERN DEM JLC"))
      (libsource (lib "ICs And Semiconductors") (part "NB6N11SMN"))
    )
    (comp (ref "R181")
      (value "0")
      (footprint "RESC1005X40N")
      (description "Resistor")
      (fields
        (field (name "PART NUMBER") "R0402_0R_JUMPER")
        (field (name "MANUFACTURER") "GENERIC")
        (field (name "AUTHOR") "CERN DEM JLC")
      )
      (libsource (lib "Resistors") (part "Resistor"))
    )
    (comp (ref "R182")
      (value "0")
      (footprint "RESC1005X40N")
      (description "Resistor")
      (fields
        (field (name "PART NUMBER") "R0402_0R_JUMPER")
        (field (name "MANUFACTURER") "GENERIC")
        (field (name "AUTHOR") "CERN DEM JLC")
      )
      (libsource (lib "Resistors") (part "Resistor"))
    )
    (comp (ref "R183")
      (value "0")
      (footprint "RESC1005X40N")
      (description "Resistor")
      (fields
        (field (name "PART NUMBER") "R0402_0R_JUMPER")
        (field (name "MANUFACTURER") "GENERIC")
        (field (name "AUTHOR") "CERN DEM JLC")
      )
      (libsource (lib "Resistors") (part "Resistor"))
    )
    (comp (ref "R184")
      (value "0")
      (footprint "RESC1005X40N")
      (description "Resistor")
      (fields
        (field (name "PART NUMBER") "R0402_0R_JUMPER")
        (field (name "MANUFACTURER") "GENERIC")
        (field (name "AUTHOR") "CERN DEM JLC")
      )
      (libsource (lib "Resistors") (part "Resistor"))
    )
    (comp (ref "R185")
      (value "0")
      (footprint "RESC1005X40N")
      (description "Resistor")
      (fields
        (field (name "PART NUMBER") "R0402_0R_JUMPER")
        (field (name "MANUFACTURER") "GENERIC")
        (field (name "AUTHOR") "CERN DEM JLC")
      )
      (libsource (lib "Resistors") (part "Resistor"))
    )
    (comp (ref "R186")
      (value "0")
      (footprint "RESC1005X40N")
      (description "Resistor")
      (fields
        (field (name "PART NUMBER") "R0402_0R_JUMPER")
        (field (name "MANUFACTURER") "GENERIC")
        (field (name "AUTHOR") "CERN DEM JLC")
      )
      (libsource (lib "Resistors") (part "Resistor"))
    )
  )
  (nets
    (net (code "8") (name "/FCLKA_N") (class "Default")
      (node (ref "C552") (pin "1") (pinfunction "1_1") (pintype "passive"))
    )
    (net (code "9") (name "/FCLKA_P") (class "Default")
      (node (ref "C1006") (pin "1") (pinfunction "1_1") (pintype "passive"))
    )
    (net (code "10") (name "/GTP4-7_CLK_IN_N") (class "Default")
      (node (ref "C801") (pin "2") (pinfunction "2_2") (pintype "passive"))
    )
    (net (code "11") (name "/GTP4-7_CLK_IN_P") (class "Default")
      (node (ref "C863") (pin "2") (pinfunction "2_2") (pintype "passive"))
    )
    (net (code "12") (name "/GTP4-7_CLK_OUT_N") (class "Default")
      (node (ref "IC29") (pin "2") (pinfunction "~{Q0}_2") (pintype "output"))
    )
    (net (code "13") (name "/GTP4-7_CLK_OUT_P") (class "Default")
      (node (ref "IC29") (pin "1") (pinfunction "Q0_1") (pintype "output"))
    )
    (net (code "14") (name "/GTP4RX_N") (class "Default")
      (node (ref "C507") (pin "2") (pinfunction "2_2") (pintype "passive"))
    )
    (net (code "15") (name "/GTP4RX_P") (class "Default")
      (node (ref "C510") (pin "2") (pinfunction "2_2") (pintype "passive"))
    )
    (net (code "16") (name "/GTP4TX_N") (class "Default")
      (node (ref "C513") (pin "2") (pinfunction "2_2") (pintype "passive"))
    )
    (net (code "17") (name "/GTP4TX_P") (class "Default")
      (node (ref "C514") (pin "2") (pinfunction "2_2") (pintype "passive"))
    )
    (net (code "18") (name "/GTP5RX_N") (class "Default")
      (node (ref "C503") (pin "2") (pinfunction "2_2") (pintype "passive"))
    )
    (net (code "19") (name "/GTP5RX_P") (class "Default")
      (node (ref "C504") (pin "2") (pinfunction "2_2") (pintype "passive"))
    )
    (net (code "20") (name "/GTP5TX_N") (class "Default")
      (node (ref "C505") (pin "2") (pinfunction "2_2") (pintype "passive"))
    )
    (net (code "21") (name "/GTP5TX_P") (class "Default")
      (node (ref "C506") (pin "2") (pinfunction "2_2") (pintype "passive"))
    )
    (net (code "22") (name "/GTP6RX_N") (class "Default")
      (node (ref "C499") (pin "2") (pinfunction "2_2") (pintype "passive"))
    )
    (net (code "23") (name "/GTP6RX_P") (class "Default")
      (node (ref "C500") (pin "2") (pinfunction "2_2") (pintype "passive"))
    )
    (net (code "24") (name "/GTP6TX_N") (class "Default")
      (node (ref "C501") (pin "2") (pinfunction "2_2") (pintype "passive"))
    )
    (net (code "25") (name "/GTP6TX_P") (class "Default")
      (node (ref "C502") (pin "2") (pinfunction "2_2") (pintype "passive"))
    )
    (net (code "26") (name "/GTP7RX_N") (class "Default")
      (node (ref "C495") (pin "2") (pinfunction "2_2") (pintype "passive"))
    )
    (net (code "27") (name "/GTP7RX_P") (class "Default")
      (node (ref "C496") (pin "2") (pinfunction "2_2") (pintype "passive"))
    )
    (net (code "28") (name "/GTP7TX_N") (class "Default")
      (node (ref "C497") (pin "2") (pinfunction "2_2") (pintype "passive"))
    )
    (net (code "29") (name "/GTP7TX_P") (class "Default")
      (node (ref "C498") (pin "2") (pinfunction "2_2") (pintype "passive"))
    )
    (net (code "30") (name "/GTP8-11_CLK_IN_N") (class "Default")
      (node (ref "C369") (pin "2") (pinfunction "2_2") (pintype "passive"))
    )
    (net (code "31") (name "/GTP8-11_CLK_IN_P") (class "Default")
      (node (ref "C371") (pin "2") (pinfunction "2_2") (pintype "passive"))
    )
    (net (code "32") (name "/GTP8-11_CLK_OUT_N") (class "Default")
      (node (ref "IC36") (pin "2") (pinfunction "~{Q0}_2") (pintype "output"))
    )
    (net (code "33") (name "/GTP8-11_CLK_OUT_P") (class "Default")
      (node (ref "IC36") (pin "1") (pinfunction "Q0_1") (pintype "output"))
    )
    (net (code "34") (name "/GTP8RX_N") (class "Default")
      (node (ref "C468") (pin "2") (pinfunction "2_2") (pintype "passive"))
    )
    (net (code "35") (name "/GTP8RX_P") (class "Default")
      (node (ref "C490") (pin "2") (pinfunction "2_2") (pintype "passive"))
    )
    (net (code "36") (name "/GTP8TX_N") (class "Default")
      (node (ref "C492") (pin "2") (pinfunction "2_2") (pintype "passive"))
    )
    (net (code "37") (name "/GTP8TX_P") (class "Default")
      (node (ref "C494") (pin "2") (pinfunction "2_2") (pintype "passive"))
    )
    (net (code "38") (name "/GTP9RX_N") (class "Default")
      (node (ref "C463") (pin "2") (pinfunction "2_2") (pintype "passive"))
    )
    (net (code "39") (name "/GTP9RX_P") (class "Default")
      (node (ref "C464") (pin "2") (pinfunction "2_2") (pintype "passive"))
    )
    (net (code "40") (name "/GTP9TX_N") (class "Default")
      (node (ref "C465") (pin "2") (pinfunction "2_2") (pintype "passive"))
    )
    (net (code "41") (name "/GTP9TX_P") (class "Default")
      (node (ref "C466") (pin "2") (pinfunction "2_2") (pintype "passive"))
    )
    (net (code "42") (name "/GTP10RX_N") (class "Default")
      (node (ref "C459") (pin "2") (pinfunction "2_2") (pintype "passive"))
    )
    (net (code "43") (name "/GTP10RX_P") (class "Default")
      (node (ref "C460") (pin "2") (pinfunction "2_2") (pintype "passive"))
    )
    (net (code "44") (name "/GTP10TX_N") (class "Default")
      (node (ref "C461") (pin "2") (pinfunction "2_2") (pintype "passive"))
    )
    (net (code "45") (name "/GTP10TX_P") (class "Default")
      (node (ref "C462") (pin "2") (pinfunction "2_2") (pintype "passive"))
    )
    (net (code "46") (name "/GTP11RX_N") (class "Default")
      (node (ref "C324") (pin "2") (pinfunction "2_2") (pintype "passive"))
    )
    (net (code "47") (name "/GTP11RX_P") (class "Default")
      (node (ref "C338") (pin "2") (pinfunction "2_2") (pintype "passive"))
    )
    (net (code "48") (name "/GTP11TX_N") (class "Default")
      (node (ref "C456") (pin "2") (pinfunction "2_2") (pintype "passive"))
    )
    (net (code "49") (name "/GTP11TX_P") (class "Default")
      (node (ref "C458") (pin "2") (pinfunction "2_2") (pintype "passive"))
    )
    (net (code "50") (name "/GTP12-15_CLK_IN_N") (class "Default")
      (node (ref "C862") (pin "2") (pinfunction "2_2") (pintype "passive"))
    )
    (net (code "51") (name "/GTP12-15_CLK_IN_P") (class "Default")
      (node (ref "C864") (pin "2") (pinfunction "2_2") (pintype "passive"))
    )
    (net (code "52") (name "/GTP12-15_CLK_OUT_N") (class "Default")
      (node (ref "IC23") (pin "2") (pinfunction "~{Q0}_2") (pintype "output"))
    )
    (net (code "53") (name "/GTP12-15_CLK_OUT_P") (class "Default")
      (node (ref "IC23") (pin "1") (pinfunction "Q0_1") (pintype "output"))
    )
    (net (code "54") (name "/GTP12RX_N") (class "Default")
      (node (ref "C508") (pin "1") (pinfunction "1_1") (pintype "passive"))
    )
    (net (code "55") (name "/GTP12RX_P") (class "Default")
      (node (ref "C511") (pin "1") (pinfunction "1_1") (pintype "passive"))
    )
    (net (code "56") (name "/GTP12TX_N") (class "Default")
      (node (ref "C509") (pin "1") (pinfunction "1_1") (pintype "passive"))
    )
    (net (code "57") (name "/GTP12TX_P") (class "Default")
      (node (ref "C512") (pin "1") (pinfunction "1_1") (pintype "passive"))
    )
    (net (code "58") (name "/GTP13RX_N") (class "Default")
      (node (ref "C515") (pin "1") (pinfunction "1_1") (pintype "passive"))
    )
    (net (code "59") (name "/GTP13RX_P") (class "Default")
      (node (ref "C517") (pin "1") (pinfunction "1_1") (pintype "passive"))
    )
    (net (code "60") (name "/GTP13TX_N") (class "Default")
      (node (ref "C516") (pin "1") (pinfunction "1_1") (pintype "passive"))
    )
    (net (code "61") (name "/GTP13TX_P") (class "Default")
      (node (ref "C518") (pin "1") (pinfunction "1_1") (pintype "passive"))
    )
    (net (code "62") (name "/GTP14RX_N") (class "Default")
      (node (ref "C519") (pin "1") (pinfunction "1_1") (pintype "passive"))
    )
    (net (code "63") (name "/GTP14RX_P") (class "Default")
      (node (ref "C521") (pin "1") (pinfunction "1_1") (pintype "passive"))
    )
    (net (code "64") (name "/GTP14TX_N") (class "Default")
      (node (ref "C520") (pin "1") (pinfunction "1_1") (pintype "passive"))
    )
    (net (code "65") (name "/GTP14TX_P") (class "Default")
      (node (ref "C765") (pin "1") (pinfunction "1_1") (pintype "passive"))
    )
    (net (code "66") (name "/GTP15RX_N") (class "Default")
      (node (ref "C321") (pin "2") (pinfunction "2_2") (pintype "passive"))
    )
    (net (code "67") (name "/GTP15RX_P") (class "Default")
      (node (ref "C326") (pin "2") (pinfunction "2_2") (pintype "passive"))
    )
    (net (code "68") (name "/GTP15TX_N") (class "Default")
      (node (ref "C455") (pin "2") (pinfunction "2_2") (pintype "passive"))
    )
    (net (code "69") (name "/GTP15TX_P") (class "Default")
      (node (ref "C457") (pin "2") (pinfunction "2_2") (pintype "passive"))
    )
    (net (code "70") (name "/GTREF0_128_N") (class "Default")
      (node (ref "C372") (pin "1") (pinfunction "1_1") (pintype "passive"))
      (node (ref "IC18") (pin "AA34") (pinfunction "MGTREFCLK0N_128_AA34") (pintype "input"))
    )
    (net (code "71") (name "/GTREF0_128_P") (class "Default")
      (node (ref "C373") (pin "1") (pinfunction "1_1") (pintype "passive"))
      (node (ref "IC18") (pin "AA33") (pinfunction "MGTREFCLK0P_128_AA33") (pintype "input"))
    )
    (net (code "72") (name "/GTREF0_129_N") (class "Default")
      (node (ref "C369") (pin "1") (pinfunction "1_1") (pintype "passive"))
      (node (ref "IC18") (pin "W34") (pinfunction "MGTREFCLK0N_129_W34") (pintype "input"))
    )
    (net (code "73") (name "/GTREF0_129_P") (class "Default")
      (node (ref "C371") (pin "1") (pinfunction "1_1") (pintype "passive"))
      (node (ref "IC18") (pin "W33") (pinfunction "MGTREFCLK0P_129_W33") (pintype "input"))
    )
    (net (code "74") (name "/GTREF0_130_N") (class "Default")
      (node (ref "C862") (pin "1") (pinfunction "1_1") (pintype "passive"))
      (node (ref "IC18") (pin "U34") (pinfunction "MGTREFCLK0N_130_U34") (pintype "input"))
    )
    (net (code "75") (name "/GTREF0_130_P") (class "Default")
      (node (ref "C864") (pin "1") (pinfunction "1_1") (pintype "passive"))
      (node (ref "IC18") (pin "U33") (pinfunction "MGTREFCLK0P_130_U33") (pintype "input"))
    )
    (net (code "76") (name "/GTREF1_128_N") (class "Default")
      (node (ref "C801") (pin "1") (pinfunction "1_1") (pintype "passive"))
      (node (ref "IC18") (pin "Y32") (pinfunction "MGTREFCLK1N_128_Y32") (pintype "input"))
    )
    (net (code "77") (name "/GTREF1_128_P") (class "Default")
      (node (ref "C863") (pin "1") (pinfunction "1_1") (pintype "passive"))
      (node (ref "IC18") (pin "Y31") (pinfunction "MGTREFCLK1P_128_Y31") (pintype "input"))
    )
    (net (code "78") (name "/GTREF1_129_N") (class "Default")
      (node (ref "C365") (pin "1") (pinfunction "1_1") (pintype "passive"))
      (node (ref "IC18") (pin "V32") (pinfunction "MGTREFCLK1N_129_V32") (pintype "input"))
    )
    (net (code "79") (name "/GTREF1_129_P") (class "Default")
      (node (ref "C367") (pin "1") (pinfunction "1_1") (pintype "passive"))
      (node (ref "IC18") (pin "V31") (pinfunction "MGTREFCLK1P_129_V31") (pintype "input"))
    )
    (net (code "80") (name "/GTREF1_130_N") (class "Default")
      (node (ref "C364") (pin "1") (pinfunction "1_1") (pintype "passive"))
      (node (ref "IC18") (pin "T32") (pinfunction "MGTREFCLK1N_130_T32") (pintype "input"))
    )
    (net (code "81") (name "/GTREF1_130_P") (class "Default")
      (node (ref "C366") (pin "1") (pinfunction "1_1") (pintype "passive"))
      (node (ref "IC18") (pin "T31") (pinfunction "MGTREFCLK1P_130_T31") (pintype "input"))
    )
    (net (code "82") (name "/GTY_128_0_RX_N") (class "Default")
      (node (ref "C513") (pin "1") (pinfunction "1_1") (pintype "passive"))
      (node (ref "IC18") (pin "Y36") (pinfunction "MGTYTXN0_128_Y36") (pintype "output"))
    )
    (net (code "83") (name "/GTY_128_0_RX_P") (class "Default")
      (node (ref "C514") (pin "1") (pinfunction "1_1") (pintype "passive"))
      (node (ref "IC18") (pin "Y35") (pinfunction "MGTYTXP0_128_Y35") (pintype "output"))
    )
    (net (code "84") (name "/GTY_128_0_TX_N") (class "Default")
      (node (ref "C507") (pin "1") (pinfunction "1_1") (pintype "passive"))
      (node (ref "IC18") (pin "AA39") (pinfunction "MGTYRXN0_128_AA39") (pintype "input"))
    )
    (net (code "85") (name "/GTY_128_0_TX_P") (class "Default")
      (node (ref "C510") (pin "1") (pinfunction "1_1") (pintype "passive"))
      (node (ref "IC18") (pin "AA38") (pinfunction "MGTYRXP0_128_AA38") (pintype "input"))
    )
    (net (code "86") (name "/GTY_128_1_RX_N") (class "Default")
      (node (ref "C505") (pin "1") (pinfunction "1_1") (pintype "passive"))
      (node (ref "IC18") (pin "V36") (pinfunction "MGTYTXN1_128_V36") (pintype "output"))
    )
    (net (code "87") (name "/GTY_128_1_RX_P") (class "Default")
      (node (ref "C506") (pin "1") (pinfunction "1_1") (pintype "passive"))
      (node (ref "IC18") (pin "V35") (pinfunction "MGTYTXP1_128_V35") (pintype "output"))
    )
    (net (code "88") (name "/GTY_128_1_TX_N") (class "Default")
      (node (ref "C503") (pin "1") (pinfunction "1_1") (pintype "passive"))
      (node (ref "IC18") (pin "W39") (pinfunction "MGTYRXN1_128_W39") (pintype "input"))
    )
    (net (code "89") (name "/GTY_128_1_TX_P") (class "Default")
      (node (ref "C504") (pin "1") (pinfunction "1_1") (pintype "passive"))
      (node (ref "IC18") (pin "W38") (pinfunction "MGTYRXP1_128_W38") (pintype "input"))
    )
    (net (code "90") (name "/GTY_128_2_RX_N") (class "Default")
      (node (ref "C501") (pin "1") (pinfunction "1_1") (pintype "passive"))
      (node (ref "IC18") (pin "T36") (pinfunction "MGTYTXN2_128_T36") (pintype "output"))
    )
    (net (code "91") (name "/GTY_128_2_RX_P") (class "Default")
      (node (ref "C502") (pin "1") (pinfunction "1_1") (pintype "passive"))
      (node (ref "IC18") (pin "T35") (pinfunction "MGTYTXP2_128_T35") (pintype "output"))
    )
    (net (code "92") (name "/GTY_128_2_TX_N") (class "Default")
      (node (ref "C499") (pin "1") (pinfunction "1_1") (pintype "passive"))
      (node (ref "IC18") (pin "U39") (pinfunction "MGTYRXN2_128_U39") (pintype "input"))
    )
    (net (code "93") (name "/GTY_128_2_TX_P") (class "Default")
      (node (ref "C500") (pin "1") (pinfunction "1_1") (pintype "passive"))
      (node (ref "IC18") (pin "U38") (pinfunction "MGTYRXP2_128_U38") (pintype "input"))
    )
    (net (code "94") (name "/GTY_128_3_RX_N") (class "Default")
      (node (ref "C497") (pin "1") (pinfunction "1_1") (pintype "passive"))
      (node (ref "IC18") (pin "R34") (pinfunction "MGTYTXN3_128_R34") (pintype "output"))
    )
    (net (code "95") (name "/GTY_128_3_RX_P") (class "Default")
      (node (ref "C498") (pin "1") (pinfunction "1_1") (pintype "passive"))
      (node (ref "IC18") (pin "R33") (pinfunction "MGTYTXP3_128_R33") (pintype "output"))
    )
    (net (code "96") (name "/GTY_128_3_TX_N") (class "Default")
      (node (ref "C495") (pin "1") (pinfunction "1_1") (pintype "passive"))
      (node (ref "IC18") (pin "R39") (pinfunction "MGTYRXN3_128_R39") (pintype "input"))
    )
    (net (code "97") (name "/GTY_128_3_TX_P") (class "Default")
      (node (ref "C496") (pin "1") (pinfunction "1_1") (pintype "passive"))
      (node (ref "IC18") (pin "R38") (pinfunction "MGTYRXP3_128_R38") (pintype "input"))
    )
    (net (code "98") (name "/GTY_129_0_RX_N") (class "Default")
      (node (ref "C468") (pin "1") (pinfunction "1_1") (pintype "passive"))
      (node (ref "IC18") (pin "N39") (pinfunction "MGTYRXN0_129_N39") (pintype "input"))
    )
    (net (code "99") (name "/GTY_129_0_RX_P") (class "Default")
      (node (ref "C490") (pin "1") (pinfunction "1_1") (pintype "passive"))
      (node (ref "IC18") (pin "N38") (pinfunction "MGTYRXP0_129_N38") (pintype "input"))
    )
    (net (code "100") (name "/GTY_129_0_TX_N") (class "Default")
      (node (ref "C492") (pin "1") (pinfunction "1_1") (pintype "passive"))
      (node (ref "IC18") (pin "P36") (pinfunction "MGTYTXN0_129_P36") (pintype "output"))
    )
    (net (code "101") (name "/GTY_129_0_TX_P") (class "Default")
      (node (ref "C494") (pin "1") (pinfunction "1_1") (pintype "passive"))
      (node (ref "IC18") (pin "P35") (pinfunction "MGTYTXP0_129_P35") (pintype "output"))
    )
    (net (code "102") (name "/GTY_129_1_RX_N") (class "Default")
      (node (ref "C463") (pin "1") (pinfunction "1_1") (pintype "passive"))
      (node (ref "IC18") (pin "M37") (pinfunction "MGTYRXN1_129_M37") (pintype "input"))
    )
    (net (code "103") (name "/GTY_129_1_RX_P") (class "Default")
      (node (ref "C464") (pin "1") (pinfunction "1_1") (pintype "passive"))
      (node (ref "IC18") (pin "M36") (pinfunction "MGTYRXP1_129_M36") (pintype "input"))
    )
    (net (code "104") (name "/GTY_129_1_TX_N") (class "Default")
      (node (ref "C465") (pin "1") (pinfunction "1_1") (pintype "passive"))
      (node (ref "IC18") (pin "N34") (pinfunction "MGTYTXN1_129_N34") (pintype "output"))
    )
    (net (code "105") (name "/GTY_129_1_TX_P") (class "Default")
      (node (ref "C466") (pin "1") (pinfunction "1_1") (pintype "passive"))
      (node (ref "IC18") (pin "N33") (pinfunction "MGTYTXP1_129_N33") (pintype "output"))
    )
    (net (code "106") (name "/GTY_129_2_RX_N") (class "Default")
      (node (ref "C459") (pin "1") (pinfunction "1_1") (pintype "passive"))
      (node (ref "IC18") (pin "L39") (pinfunction "MGTYRXN2_129_L39") (pintype "input"))
    )
    (net (code "107") (name "/GTY_129_2_RX_P") (class "Default")
      (node (ref "C460") (pin "1") (pinfunction "1_1") (pintype "passive"))
      (node (ref "IC18") (pin "L38") (pinfunction "MGTYRXP2_129_L38") (pintype "input"))
    )
    (net (code "108") (name "/GTY_129_2_TX_N") (class "Default")
      (node (ref "C461") (pin "1") (pinfunction "1_1") (pintype "passive"))
      (node (ref "IC18") (pin "L34") (pinfunction "MGTYTXN2_129_L34") (pintype "output"))
    )
    (net (code "109") (name "/GTY_129_2_TX_P") (class "Default")
      (node (ref "C462") (pin "1") (pinfunction "1_1") (pintype "passive"))
      (node (ref "IC18") (pin "L33") (pinfunction "MGTYTXP2_129_L33") (pintype "output"))
    )
    (net (code "110") (name "/GTY_129_3_RX_N") (class "Default")
      (node (ref "C324") (pin "1") (pinfunction "1_1") (pintype "passive"))
      (node (ref "IC18") (pin "K37") (pinfunction "MGTYRXN3_129_K37") (pintype "input"))
    )
    (net (code "111") (name "/GTY_129_3_RX_P") (class "Default")
      (node (ref "C338") (pin "1") (pinfunction "1_1") (pintype "passive"))
      (node (ref "IC18") (pin "K36") (pinfunction "MGTYRXP3_129_K36") (pintype "input"))
    )
    (net (code "112") (name "/GTY_129_3_TX_N") (class "Default")
      (node (ref "C456") (pin "1") (pinfunction "1_1") (pintype "passive"))
      (node (ref "IC18") (pin "J34") (pinfunction "MGTYTXN3_129_J34") (pintype "output"))
    )
    (net (code "113") (name "/GTY_129_3_TX_P") (class "Default")
      (node (ref "C458") (pin "1") (pinfunction "1_1") (pintype "passive"))
      (node (ref "IC18") (pin "J33") (pinfunction "MGTYTXP3_129_J33") (pintype "output"))
    )
    (net (code "114") (name "/GTY_130_0_RXC_N") (class "Default")
      (node (ref "C508") (pin "2") (pinfunction "2_2") (pintype "passive"))
      (node (ref "IC18") (pin "J39") (pinfunction "MGTYRXN0_130_J39") (pintype "input"))
    )
    (net (code "115") (name "/GTY_130_0_RXC_P") (class "Default")
      (node (ref "C511") (pin "2") (pinfunction "2_2") (pintype "passive"))
      (node (ref "IC18") (pin "J38") (pinfunction "MGTYRXP0_130_J38") (pintype "input"))
    )
    (net (code "116") (name "/GTY_130_0_TXC_N") (class "Default")
      (node (ref "C509") (pin "2") (pinfunction "2_2") (pintype "passive"))
      (node (ref "IC18") (pin "H32") (pinfunction "MGTYTXN0_130_H32") (pintype "output"))
    )
    (net (code "117") (name "/GTY_130_0_TXC_P") (class "Default")
      (node (ref "C512") (pin "2") (pinfunction "2_2") (pintype "passive"))
      (node (ref "IC18") (pin "H31") (pinfunction "MGTYTXP0_130_H31") (pintype "output"))
    )
    (net (code "118") (name "/GTY_130_1_RXC_N") (class "Default")
      (node (ref "C515") (pin "2") (pinfunction "2_2") (pintype "passive"))
      (node (ref "IC18") (pin "H37") (pinfunction "MGTYRXN1_130_H37") (pintype "input"))
    )
    (net (code "119") (name "/GTY_130_1_RXC_P") (class "Default")
      (node (ref "C517") (pin "2") (pinfunction "2_2") (pintype "passive"))
      (node (ref "IC18") (pin "H36") (pinfunction "MGTYRXP1_130_H36") (pintype "input"))
    )
    (net (code "120") (name "/GTY_130_1_TXC_N") (class "Default")
      (node (ref "C516") (pin "2") (pinfunction "2_2") (pintype "passive"))
      (node (ref "IC18") (pin "G34") (pinfunction "MGTYTXN1_130_G34") (pintype "output"))
    )
    (net (code "121") (name "/GTY_130_1_TXC_P") (class "Default")
      (node (ref "C518") (pin "2") (pinfunction "2_2") (pintype "passive"))
      (node (ref "IC18") (pin "G33") (pinfunction "MGTYTXP1_130_G33") (pintype "output"))
    )
    (net (code "122") (name "/GTY_130_2_RXC_N") (class "Default")
      (node (ref "C519") (pin "2") (pinfunction "2_2") (pintype "passive"))
      (node (ref "C869") (pin "1") (pinfunction "1_1") (pintype "passive"))
      (node (ref "IC18") (pin "G39") (pinfunction "MGTYRXN2_130_G39") (pintype "input"))
    )
    (net (code "123") (name "/GTY_130_2_RXC_P") (class "Default")
      (node (ref "C521") (pin "2") (pinfunction "2_2") (pintype "passive"))
      (node (ref "C870") (pin "1") (pinfunction "1_1") (pintype "passive"))
      (node (ref "IC18") (pin "G38") (pinfunction "MGTYRXP2_130_G38") (pintype "input"))
    )
    (net (code "124") (name "/GTY_130_2_TXC_N") (class "Default")
      (node (ref "C520") (pin "2") (pinfunction "2_2") (pintype "passive"))
      (node (ref "C871") (pin "1") (pinfunction "1_1") (pintype "passive"))
      (node (ref "IC18") (pin "F32") (pinfunction "MGTYTXN2_130_F32") (pintype "output"))
    )
    (net (code "125") (name "/GTY_130_2_TXC_P") (class "Default")
      (node (ref "C765") (pin "2") (pinfunction "2_2") (pintype "passive"))
      (node (ref "C872") (pin "1") (pinfunction "1_1") (pintype "passive"))
      (node (ref "IC18") (pin "F31") (pinfunction "MGTYTXP2_130_F31") (pintype "output"))
    )
    (net (code "126") (name "/GTY_130_3_RXC_N") (class "Default")
      (node (ref "C321") (pin "1") (pinfunction "1_1") (pintype "passive"))
      (node (ref "IC18") (pin "F37") (pinfunction "MGTYRXN3_130_F37") (pintype "input"))
    )
    (net (code "127") (name "/GTY_130_3_RXC_P") (class "Default")
      (node (ref "C326") (pin "1") (pinfunction "1_1") (pintype "passive"))
      (node (ref "IC18") (pin "F36") (pinfunction "MGTYRXP3_130_F36") (pintype "input"))
    )
    (net (code "128") (name "/GTY_130_3_TXC_N") (class "Default")
      (node (ref "C455") (pin "1") (pinfunction "1_1") (pintype "passive"))
      (node (ref "IC18") (pin "E34") (pinfunction "MGTYTXN3_130_E34") (pintype "output"))
    )
    (net (code "129") (name "/GTY_130_3_TXC_P") (class "Default")
      (node (ref "C457") (pin "1") (pinfunction "1_1") (pintype "passive"))
      (node (ref "IC18") (pin "E33") (pinfunction "MGTYTXP3_130_E33") (pintype "output"))
    )
    (net (code "130") (name "/GTY_131_0_RXC_N") (class "Default")
      (node (ref "C920") (pin "1") (pinfunction "1_1") (pintype "passive"))
      (node (ref "IC18") (pin "E39") (pinfunction "MGTYRXN0_131_E39") (pintype "input"))
    )
    (net (code "131") (name "/GTY_131_0_RXC_P") (class "Default")
      (node (ref "C919") (pin "1") (pinfunction "1_1") (pintype "passive"))
      (node (ref "IC18") (pin "E38") (pinfunction "MGTYRXP0_131_E38") (pintype "input"))
    )
    (net (code "132") (name "/GTY_131_0_TXC_N") (class "Default")
      (node (ref "C921") (pin "1") (pinfunction "1_1") (pintype "passive"))
      (node (ref "IC18") (pin "D32") (pinfunction "MGTYTXN0_131_D32") (pintype "output"))
    )
    (net (code "133") (name "/GTY_131_0_TXC_P") (class "Default")
      (node (ref "C922") (pin "1") (pinfunction "1_1") (pintype "passive"))
      (node (ref "IC18") (pin "D31") (pinfunction "MGTYTXP0_131_D31") (pintype "output"))
    )
    (net (code "134") (name "/GTY_131_1_RXC_N") (class "Default")
      (node (ref "C916") (pin "1") (pinfunction "1_1") (pintype "passive"))
      (node (ref "IC18") (pin "D37") (pinfunction "MGTYRXN1_131_D37") (pintype "input"))
    )
    (net (code "135") (name "/GTY_131_1_RXC_P") (class "Default")
      (node (ref "C915") (pin "1") (pinfunction "1_1") (pintype "passive"))
      (node (ref "IC18") (pin "D36") (pinfunction "MGTYRXP1_131_D36") (pintype "input"))
    )
    (net (code "136") (name "/GTY_131_1_TXC_N") (class "Default")
      (node (ref "C917") (pin "1") (pinfunction "1_1") (pintype "passive"))
      (node (ref "IC18") (pin "C34") (pinfunction "MGTYTXN1_131_C34") (pintype "output"))
    )
    (net (code "137") (name "/GTY_131_1_TXC_P") (class "Default")
      (node (ref "C918") (pin "1") (pinfunction "1_1") (pintype "passive"))
      (node (ref "IC18") (pin "C33") (pinfunction "MGTYTXP1_131_C33") (pintype "output"))
    )
    (net (code "138") (name "/GTY_131_2_RXC_N") (class "Default")
      (node (ref "C882") (pin "1") (pinfunction "1_1") (pintype "passive"))
      (node (ref "IC18") (pin "C39") (pinfunction "MGTYRXN2_131_C39") (pintype "input"))
    )
    (net (code "139") (name "/GTY_131_2_RXC_P") (class "Default")
      (node (ref "C881") (pin "1") (pinfunction "1_1") (pintype "passive"))
      (node (ref "IC18") (pin "C38") (pinfunction "MGTYRXP2_131_C38") (pintype "input"))
    )
    (net (code "140") (name "/GTY_131_2_TXC_N") (class "Default")
      (node (ref "C883") (pin "1") (pinfunction "1_1") (pintype "passive"))
      (node (ref "IC18") (pin "B32") (pinfunction "MGTYTXN2_131_B32") (pintype "output"))
    )
    (net (code "141") (name "/GTY_131_2_TXC_P") (class "Default")
      (node (ref "C884") (pin "1") (pinfunction "1_1") (pintype "passive"))
      (node (ref "IC18") (pin "B31") (pinfunction "MGTYTXP2_131_B31") (pintype "output"))
    )
    (net (code "142") (name "/GTY_131_3_RXC_N") (class "Default")
      (node (ref "C878") (pin "1") (pinfunction "1_1") (pintype "passive"))
      (node (ref "IC18") (pin "B37") (pinfunction "MGTYRXN3_131_B37") (pintype "input"))
    )
    (net (code "143") (name "/GTY_131_3_RXC_P") (class "Default")
      (node (ref "C877") (pin "1") (pinfunction "1_1") (pintype "passive"))
      (node (ref "IC18") (pin "B36") (pinfunction "MGTYRXP3_131_B36") (pintype "input"))
    )
    (net (code "144") (name "/GTY_131_3_TXC_N") (class "Default")
      (node (ref "C879") (pin "1") (pinfunction "1_1") (pintype "passive"))
      (node (ref "IC18") (pin "A34") (pinfunction "MGTYTXN3_131_A34") (pintype "output"))
    )
    (net (code "145") (name "/GTY_131_3_TXC_P") (class "Default")
      (node (ref "C880") (pin "1") (pinfunction "1_1") (pintype "passive"))
      (node (ref "IC18") (pin "A33") (pinfunction "MGTYTXP3_131_A33") (pintype "output"))
    )
    (net (code "146") (name "/GTY_REF_128_C_N") (class "Default")
      (node (ref "C372") (pin "2") (pinfunction "2_2") (pintype "passive"))
      (node (ref "IC29") (pin "4") (pinfunction "~{Q1}_4") (pintype "output"))
    )
    (net (code "147") (name "/GTY_REF_128_C_P") (class "Default")
      (node (ref "C373") (pin "2") (pinfunction "2_2") (pintype "passive"))
      (node (ref "IC29") (pin "3") (pinfunction "Q1_3") (pintype "output"))
    )
    (net (code "148") (name "/GTY_REF_128_N") (class "Default")
      (node (ref "IC29") (pin "10") (pinfunction "~{D}_10") (pintype "input"))
    )
    (net (code "149") (name "/GTY_REF_128_P") (class "Default")
      (node (ref "IC29") (pin "11") (pinfunction "D_11") (pintype "input"))
    )
    (net (code "150") (name "/GTY_REF_129_C_N") (class "Default")
      (node (ref "C365") (pin "2") (pinfunction "2_2") (pintype "passive"))
      (node (ref "IC36") (pin "4") (pinfunction "~{Q1}_4") (pintype "output"))
    )
    (net (code "151") (name "/GTY_REF_129_C_P") (class "Default")
      (node (ref "C367") (pin "2") (pinfunction "2_2") (pintype "passive"))
      (node (ref "IC36") (pin "3") (pinfunction "Q1_3") (pintype "output"))
    )
    (net (code "152") (name "/GTY_REF_129_N") (class "Default")
      (node (ref "IC36") (pin "10") (pinfunction "~{D}_10") (pintype "input"))
    )
    (net (code "153") (name "/GTY_REF_129_P") (class "Default")
      (node (ref "IC36") (pin "11") (pinfunction "D_11") (pintype "input"))
    )
    (net (code "154") (name "/GTY_REF_130_C_N") (class "Default")
      (node (ref "C364") (pin "2") (pinfunction "2_2") (pintype "passive"))
      (node (ref "IC23") (pin "4") (pinfunction "~{Q1}_4") (pintype "output"))
    )
    (net (code "155") (name "/GTY_REF_130_C_P") (class "Default")
      (node (ref "C366") (pin "2") (pinfunction "2_2") (pintype "passive"))
      (node (ref "IC23") (pin "3") (pinfunction "Q1_3") (pintype "output"))
    )
    (net (code "156") (name "/GTY_REF_130_N") (class "Default")
      (node (ref "IC23") (pin "10") (pinfunction "~{D}_10") (pintype "input"))
    )
    (net (code "157") (name "/GTY_REF_130_P") (class "Default")
      (node (ref "IC23") (pin "11") (pinfunction "D_11") (pintype "input"))
    )
    (net (code "158") (name "/GTY_REF_131_N") (class "Default")
      (node (ref "C370") (pin "1") (pinfunction "1_1") (pintype "passive"))
    )
    (net (code "159") (name "/GTY_REF_131_P") (class "Default")
      (node (ref "C368") (pin "1") (pinfunction "1_1") (pintype "passive"))
    )
    (net (code "160") (name "/REF_CLK_131_0_N") (class "Default")
      (node (ref "C368") (pin "2") (pinfunction "2_2") (pintype "passive"))
      (node (ref "IC18") (pin "P32") (pinfunction "MGTREFCLK0N_131_P32") (pintype "input"))
    )
    (net (code "161") (name "/REF_CLK_131_0_P") (class "Default")
      (node (ref "C370") (pin "2") (pinfunction "2_2") (pintype "passive"))
      (node (ref "IC18") (pin "P31") (pinfunction "MGTREFCLK0P_131_P31") (pintype "input"))
    )
    (net (code "162") (name "/REF_CLK_131_1_N") (class "Default")
      (node (ref "C552") (pin "2") (pinfunction "2_2") (pintype "passive"))
      (node (ref "IC18") (pin "M32") (pinfunction "MGTREFCLK1N_131_M32") (pintype "input"))
    )
    (net (code "163") (name "/REF_CLK_131_1_P") (class "Default")
      (node (ref "C1006") (pin "2") (pinfunction "2_2") (pintype "passive"))
      (node (ref "IC18") (pin "M31") (pinfunction "MGTREFCLK1P_131_M31") (pintype "input"))
    )
    (net (code "164") (name "/Rx0_N") (class "Default")
      (node (ref "C869") (pin "2") (pinfunction "2_2") (pintype "passive"))
    )
    (net (code "165") (name "/Rx0_P") (class "Default")
      (node (ref "C870") (pin "2") (pinfunction "2_2") (pintype "passive"))
    )
    (net (code "166") (name "/Rx4_N") (class "Default")
      (node (ref "C878") (pin "2") (pinfunction "2_2") (pintype "passive"))
    )
    (net (code "167") (name "/Rx4_P") (class "Default")
      (node (ref "C877") (pin "2") (pinfunction "2_2") (pintype "passive"))
    )
    (net (code "168") (name "/Rx5_N") (class "Default")
      (node (ref "C882") (pin "2") (pinfunction "2_2") (pintype "passive"))
    )
    (net (code "169") (name "/Rx5_P") (class "Default")
      (node (ref "C881") (pin "2") (pinfunction "2_2") (pintype "passive"))
    )
    (net (code "170") (name "/Rx6_N") (class "Default")
      (node (ref "C916") (pin "2") (pinfunction "2_2") (pintype "passive"))
    )
    (net (code "171") (name "/Rx6_P") (class "Default")
      (node (ref "C915") (pin "2") (pinfunction "2_2") (pintype "passive"))
    )
    (net (code "172") (name "/Rx7_N") (class "Default")
      (node (ref "C920") (pin "2") (pinfunction "2_2") (pintype "passive"))
    )
    (net (code "173") (name "/Rx7_P") (class "Default")
      (node (ref "C919") (pin "2") (pinfunction "2_2") (pintype "passive"))
    )
    (net (code "174") (name "/Tx0_N") (class "Default")
      (node (ref "C871") (pin "2") (pinfunction "2_2") (pintype "passive"))
    )
    (net (code "175") (name "/Tx0_P") (class "Default")
      (node (ref "C872") (pin "2") (pinfunction "2_2") (pintype "passive"))
    )
    (net (code "176") (name "/Tx4_N") (class "Default")
      (node (ref "C879") (pin "2") (pinfunction "2_2") (pintype "passive"))
    )
    (net (code "177") (name "/Tx4_P") (class "Default")
      (node (ref "C880") (pin "2") (pinfunction "2_2") (pintype "passive"))
    )
    (net (code "178") (name "/Tx5_N") (class "Default")
      (node (ref "C883") (pin "2") (pinfunction "2_2") (pintype "passive"))
    )
    (net (code "179") (name "/Tx5_P") (class "Default")
      (node (ref "C884") (pin "2") (pinfunction "2_2") (pintype "passive"))
    )
    (net (code "180") (name "/Tx6_N") (class "Default")
      (node (ref "C917") (pin "2") (pinfunction "2_2") (pintype "passive"))
    )
    (net (code "181") (name "/Tx6_P") (class "Default")
      (node (ref "C918") (pin "2") (pinfunction "2_2") (pintype "passive"))
    )
    (net (code "182") (name "/Tx7_N") (class "Default")
      (node (ref "C921") (pin "2") (pinfunction "2_2") (pintype "passive"))
    )
    (net (code "183") (name "/Tx7_P") (class "Default")
      (node (ref "C922") (pin "2") (pinfunction "2_2") (pintype "passive"))
    )
    (net (code "191") (name "GND") (class "Default")
      (node (ref "C892") (pin "2") (pinfunction "2_2") (pintype "passive"))
      (node (ref "C895") (pin "1") (pinfunction "1_1") (pintype "passive"))
      (node (ref "C896") (pin "2") (pinfunction "2_2") (pintype "passive"))
      (node (ref "C905") (pin "1") (pinfunction "1_1") (pintype "passive"))
      (node (ref "C906") (pin "2") (pinfunction "2_2") (pintype "passive"))
      (node (ref "C907") (pin "1") (pinfunction "1_1") (pintype "passive"))
      (node (ref "IC23") (pin "17") (pinfunction "EP_17") (pintype "power_in"))
      (node (ref "IC23") (pin "7") (pinfunction "VEE_7") (pintype "power_in"))
      (node (ref "IC23") (pin "8") (pinfunction "VEE_8") (pintype "power_in"))
      (node (ref "IC29") (pin "17") (pinfunction "EP_17") (pintype "power_in"))
      (node (ref "IC29") (pin "7") (pinfunction "VEE_7") (pintype "power_in"))
      (node (ref "IC29") (pin "8") (pinfunction "VEE_8") (pintype "power_in"))
      (node (ref "IC36") (pin "17") (pinfunction "EP_17") (pintype "power_in"))
      (node (ref "IC36") (pin "7") (pinfunction "VEE_7") (pintype "power_in"))
      (node (ref "IC36") (pin "8") (pinfunction "VEE_8") (pintype "power_in"))
    )
    (net (code "192") (name "Net-(IC23-VTD)") (class "Default")
      (node (ref "IC23") (pin "12") (pinfunction "VTD_12") (pintype "passive"))
      (node (ref "R181") (pin "2") (pinfunction "2_2") (pintype "passive"))
    )
    (net (code "193") (name "Net-(IC23-~{VTD})") (class "Default")
      (node (ref "IC23") (pin "9") (pinfunction "~{VTD}_9") (pintype "passive"))
      (node (ref "R183") (pin "2") (pinfunction "2_2") (pintype "passive"))
    )
    (net (code "194") (name "Net-(IC29-VTD)") (class "Default")
      (node (ref "IC29") (pin "12") (pinfunction "VTD_12") (pintype "passive"))
      (node (ref "R182") (pin "2") (pinfunction "2_2") (pintype "passive"))
    )
    (net (code "195") (name "Net-(IC29-~{VTD})") (class "Default")
      (node (ref "IC29") (pin "9") (pinfunction "~{VTD}_9") (pintype "passive"))
      (node (ref "R185") (pin "2") (pinfunction "2_2") (pintype "passive"))
    )
    (net (code "196") (name "Net-(IC36-VTD)") (class "Default")
      (node (ref "IC36") (pin "12") (pinfunction "VTD_12") (pintype "passive"))
      (node (ref "R184") (pin "2") (pinfunction "2_2") (pintype "passive"))
    )
    (net (code "197") (name "Net-(IC36-~{VTD})") (class "Default")
      (node (ref "IC36") (pin "9") (pinfunction "~{VTD}_9") (pintype "passive"))
      (node (ref "R186") (pin "2") (pinfunction "2_2") (pintype "passive"))
    )
    (net (code "198") (name "Net-(R181-Pad1)") (class "Default")
      (node (ref "R181") (pin "1") (pinfunction "1_1") (pintype "passive"))
      (node (ref "R183") (pin "1") (pinfunction "1_1") (pintype "passive"))
    )
    (net (code "199") (name "Net-(R182-Pad1)") (class "Default")
      (node (ref "R182") (pin "1") (pinfunction "1_1") (pintype "passive"))
      (node (ref "R185") (pin "1") (pinfunction "1_1") (pintype "passive"))
    )
    (net (code "200") (name "Net-(R184-Pad1)") (class "Default")
      (node (ref "R184") (pin "1") (pinfunction "1_1") (pintype "passive"))
      (node (ref "R186") (pin "1") (pinfunction "1_1") (pintype "passive"))
    )
    (net (code "201") (name "P3V3_CLK") (class "Default")
      (node (ref "C892") (pin "1") (pinfunction "1_1") (pintype "passive"))
      (node (ref "C895") (pin "2") (pinfunction "2_2") (pintype "passive"))
      (node (ref "C896") (pin "1") (pinfunction "1_1") (pintype "passive"))
      (node (ref "C905") (pin "2") (pinfunction "2_2") (pintype "passive"))
      (node (ref "C906") (pin "1") (pinfunction "1_1") (pintype "passive"))
      (node (ref "C907") (pin "2") (pinfunction "2_2") (pintype "passive"))
      (node (ref "IC23") (pin "13") (pinfunction "VCC_13") (pintype "power_in"))
      (node (ref "IC23") (pin "14") (pinfunction "VCC_14") (pintype "power_in"))
      (node (ref "IC23") (pin "15") (pinfunction "VCC_15") (pintype "power_in"))
      (node (ref "IC23") (pin "16") (pinfunction "VCC_16") (pintype "power_in"))
      (node (ref "IC23") (pin "5") (pinfunction "VCC_5") (pintype "power_in"))
      (node (ref "IC29") (pin "13") (pinfunction "VCC_13") (pintype "power_in"))
      (node (ref "IC29") (pin "14") (pinfunction "VCC_14") (pintype "power_in"))
      (node (ref "IC29") (pin "15") (pinfunction "VCC_15") (pintype "power_in"))
      (node (ref "IC29") (pin "16") (pinfunction "VCC_16") (pintype "power_in"))
      (node (ref "IC29") (pin "5") (pinfunction "VCC_5") (pintype "power_in"))
      (node (ref "IC36") (pin "13") (pinfunction "VCC_13") (pintype "power_in"))
      (node (ref "IC36") (pin "14") (pinfunction "VCC_14") (pintype "power_in"))
      (node (ref "IC36") (pin "15") (pinfunction "VCC_15") (pintype "power_in"))
      (node (ref "IC36") (pin "16") (pinfunction "VCC_16") (pintype "power_in"))
      (node (ref "IC36") (pin "5") (pinfunction "VCC_5") (pintype "power_in"))
    )
    (net (code "202") (name "unconnected-(IC23-NC-Pad6)") (class "Default")
      (node (ref "IC23") (pin "6") (pinfunction "NC_6") (pintype "passive"))
    )
    (net (code "203") (name "unconnected-(IC29-NC-Pad6)") (class "Default")
      (node (ref "IC29") (pin "6") (pinfunction "NC_6") (pintype "passive"))
    )
    (net (code "204") (name "unconnected-(IC36-NC-Pad6)") (class "Default")
      (node (ref "IC36") (pin "6") (pinfunction "NC_6") (pintype "passive"))
    )
  )
)
